# isolatedPowerSwitchingModule.net
KiCad netlist of a schematic drawn in EAGLE
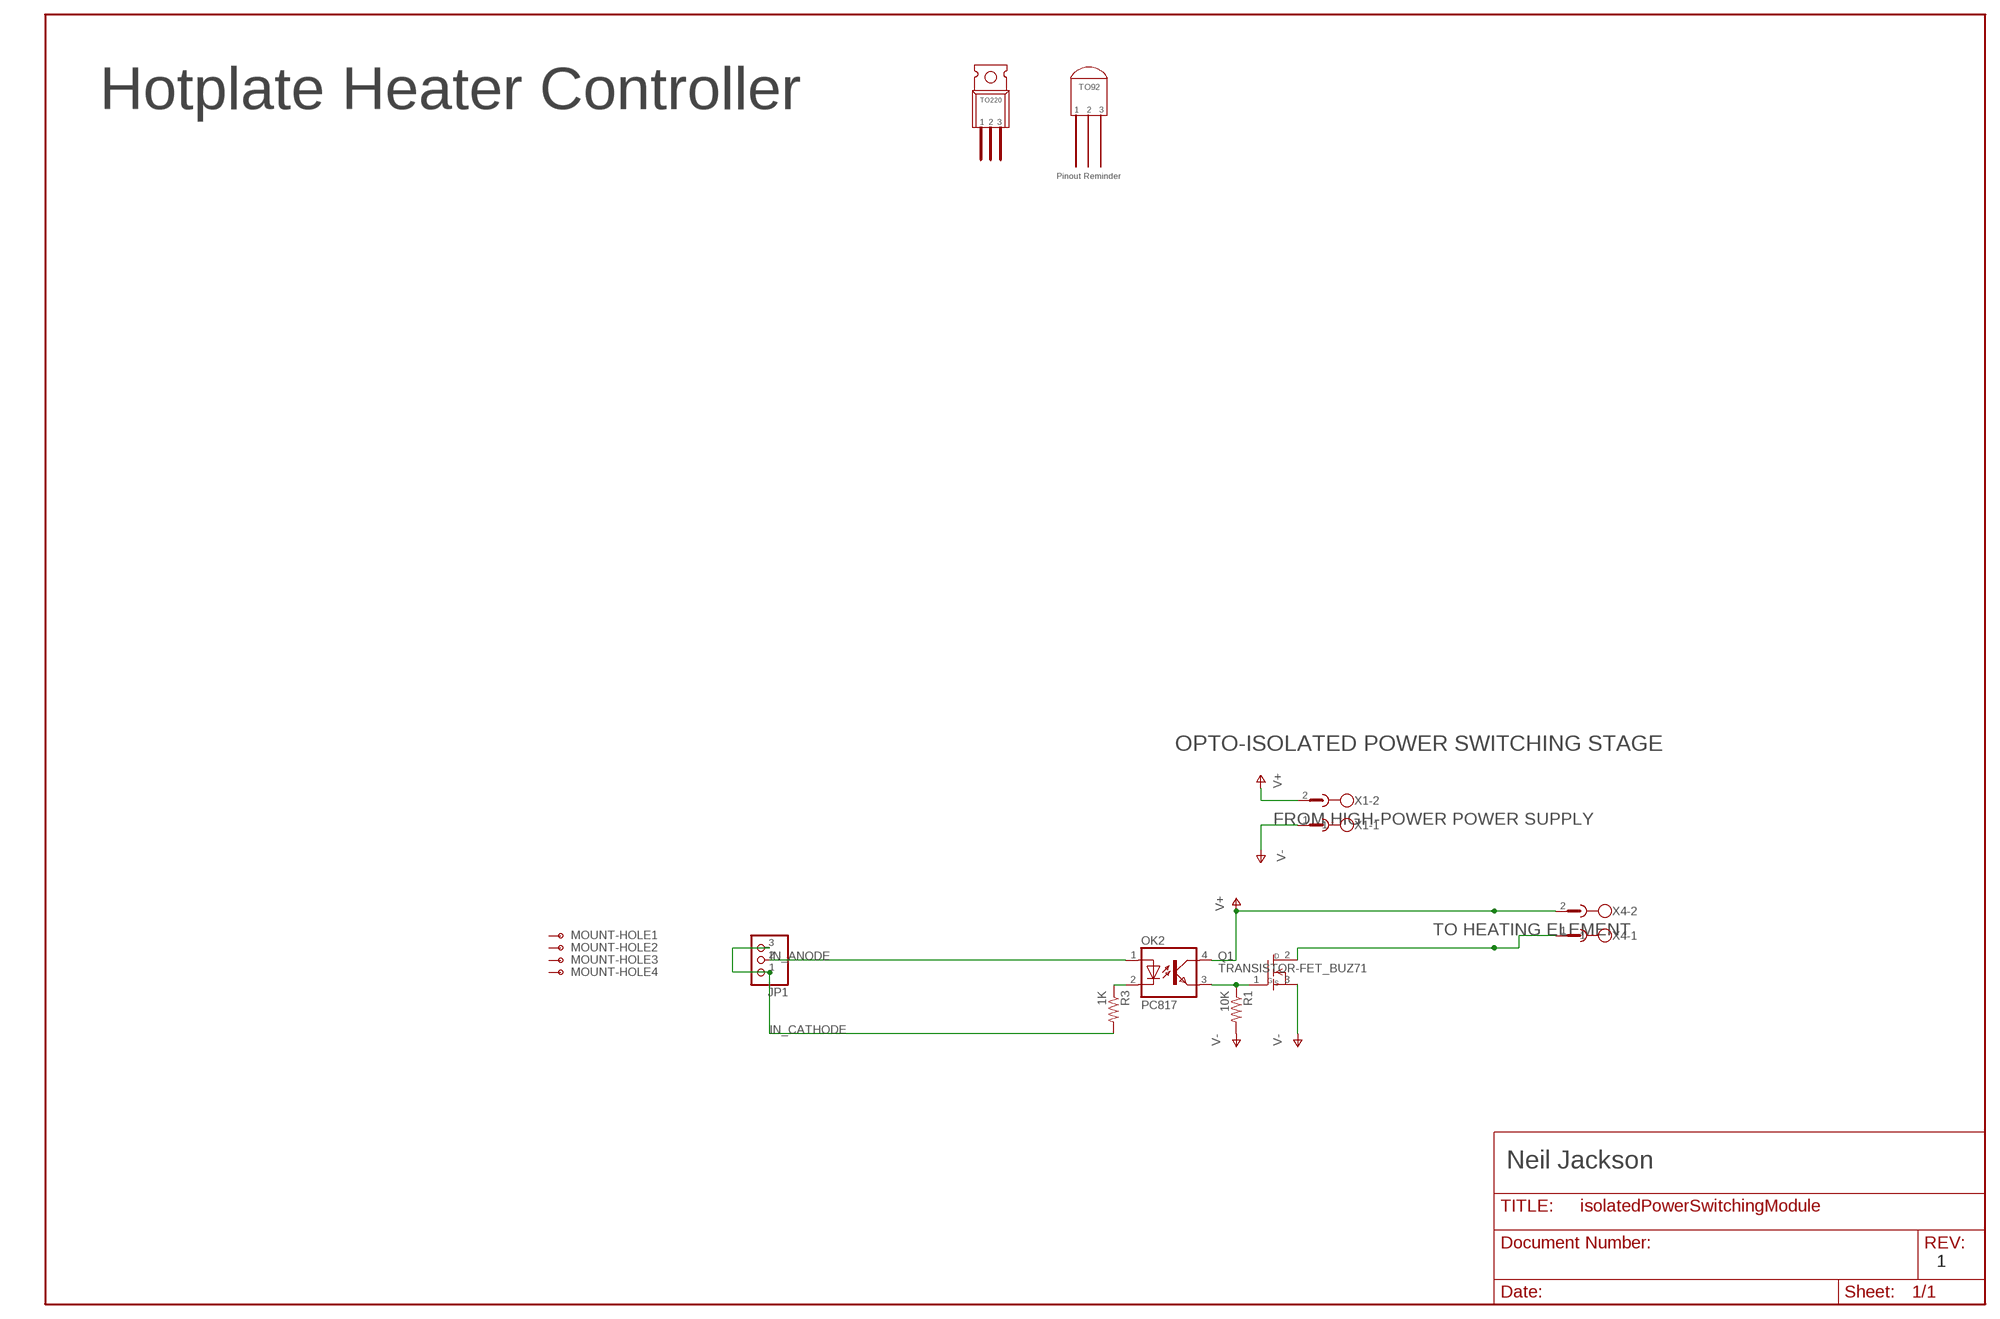
[diagram p0: schematic, sheet 1]

(export (version "E")
  (design (tool "Eeschema 10.0.6"))
  (components
    (comp (ref "JP1")
      (value "PINHD-1X3")
      (footprint "eagle-import:1X03")
      (libsource (lib "eagle-import") (part "PINHD-1X3"))
    )
    (comp (ref "MOUNT-HOLE1")
      (value "MOUNT-HOLE")
      (footprint "eagle-import:8-32")
      (libsource (lib "eagle-import") (part "MOUNT-HOLE"))
    )
    (comp (ref "MOUNT-HOLE2")
      (value "MOUNT-HOLE")
      (footprint "eagle-import:8-32")
      (libsource (lib "eagle-import") (part "MOUNT-HOLE"))
    )
    (comp (ref "MOUNT-HOLE3")
      (value "MOUNT-HOLE")
      (footprint "eagle-import:8-32")
      (libsource (lib "eagle-import") (part "MOUNT-HOLE"))
    )
    (comp (ref "MOUNT-HOLE4")
      (value "MOUNT-HOLE")
      (footprint "eagle-import:8-32")
      (libsource (lib "eagle-import") (part "MOUNT-HOLE"))
    )
    (comp (ref "OK2")
      (value "PC817")
      (footprint "eagle-import:DIL04")
      (fields (field (name "MPN") "PC817X4J000F"))
      (libsource (lib "eagle-import") (part "PC817"))
    )
    (comp (ref "Q1")
      (value "TRANSISTOR-FET_BUZ71")
      (footprint "eagle-import:TRANSISTOR-FET_TO220")
      (libsource (lib "eagle-import") (part "TRANSISTOR-FET_BUZ71"))
    )
    (comp (ref "R1")
      (value "10K")
      (footprint "eagle-import:0207_10")
      (libsource (lib "eagle-import") (part "R-US_0207/10"))
    )
    (comp (ref "R3")
      (value "1K")
      (footprint "eagle-import:0207_10")
      (libsource (lib "eagle-import") (part "R-US_0207/10"))
    )
    (comp (ref "X1")
      (value "PIN_HEADER_2_CONDUCTORRIGHTANGLE")
      (footprint "eagle-import:MSTBA2")
      (libsource (lib "eagle-import") (part "PIN_HEADER_2_CONDUCTORRIGHTANGLE"))
    )
    (comp (ref "X4")
      (value "PIN_HEADER_2_CONDUCTORRIGHTANGLE")
      (footprint "eagle-import:MSTBA2")
      (libsource (lib "eagle-import") (part "PIN_HEADER_2_CONDUCTORRIGHTANGLE"))
    )
  )
  (nets
    (net (code "1") (name "/IN_ANODE") (class "Default")
      (node (ref "JP1") (pin "2") (pinfunction "2_2") (pintype "passive"))
      (node (ref "OK2") (pin "1") (pinfunction "A_1") (pintype "passive"))
    )
    (net (code "2") (name "/IN_CATHODE") (class "Default")
      (node (ref "JP1") (pin "1") (pinfunction "1_1") (pintype "passive"))
      (node (ref "JP1") (pin "3") (pinfunction "3_3") (pintype "passive"))
      (node (ref "R3") (pin "2") (pinfunction "2_2") (pintype "passive"))
    )
    (net (code "3") (name "Net-(OK2-C)") (class "Default")
      (node (ref "OK2") (pin "2") (pinfunction "C_2") (pintype "passive"))
      (node (ref "R3") (pin "1") (pinfunction "1_1") (pintype "passive"))
    )
    (net (code "4") (name "Net-(OK2-EMIT)") (class "Default")
      (node (ref "OK2") (pin "3") (pinfunction "EMIT_3") (pintype "passive"))
      (node (ref "Q1") (pin "1") (pinfunction "G_1") (pintype "passive"))
      (node (ref "R1") (pin "1") (pinfunction "1_1") (pintype "passive"))
    )
    (net (code "5") (name "Net-(Q1-D)") (class "Default")
      (node (ref "Q1") (pin "2") (pinfunction "D_2") (pintype "passive"))
      (node (ref "X4") (pin "1") (pinfunction "1_1") (pintype "passive"))
    )
    (net (code "6") (name "V+") (class "Default")
      (node (ref "OK2") (pin "4") (pinfunction "COL_4") (pintype "passive"))
      (node (ref "X1") (pin "2") (pinfunction "1_2") (pintype "passive"))
      (node (ref "X4") (pin "2") (pinfunction "1_2") (pintype "passive"))
    )
    (net (code "7") (name "V-") (class "Default")
      (node (ref "Q1") (pin "3") (pinfunction "S_3") (pintype "passive"))
      (node (ref "R1") (pin "2") (pinfunction "2_2") (pintype "passive"))
      (node (ref "X1") (pin "1") (pinfunction "1_1") (pintype "passive"))
    )
    (net (code "8") (name "unconnected-(MOUNT-HOLE1-MOUNT_HOLE-Pad1)") (class "Default")
      (node (ref "MOUNT-HOLE1") (pin "1") (pinfunction "MOUNT_HOLE_1") (pintype "bidirectional"))
    )
    (net (code "9") (name "unconnected-(MOUNT-HOLE2-MOUNT_HOLE-Pad1)") (class "Default")
      (node (ref "MOUNT-HOLE2") (pin "1") (pinfunction "MOUNT_HOLE_1") (pintype "bidirectional"))
    )
    (net (code "10") (name "unconnected-(MOUNT-HOLE3-MOUNT_HOLE-Pad1)") (class "Default")
      (node (ref "MOUNT-HOLE3") (pin "1") (pinfunction "MOUNT_HOLE_1") (pintype "bidirectional"))
    )
    (net (code "11") (name "unconnected-(MOUNT-HOLE4-MOUNT_HOLE-Pad1)") (class "Default")
      (node (ref "MOUNT-HOLE4") (pin "1") (pinfunction "MOUNT_HOLE_1") (pintype "bidirectional"))
    )
  )
)
